# 4_digit_seven_segment.net
KiCad netlist of a schematic drawn in EAGLE
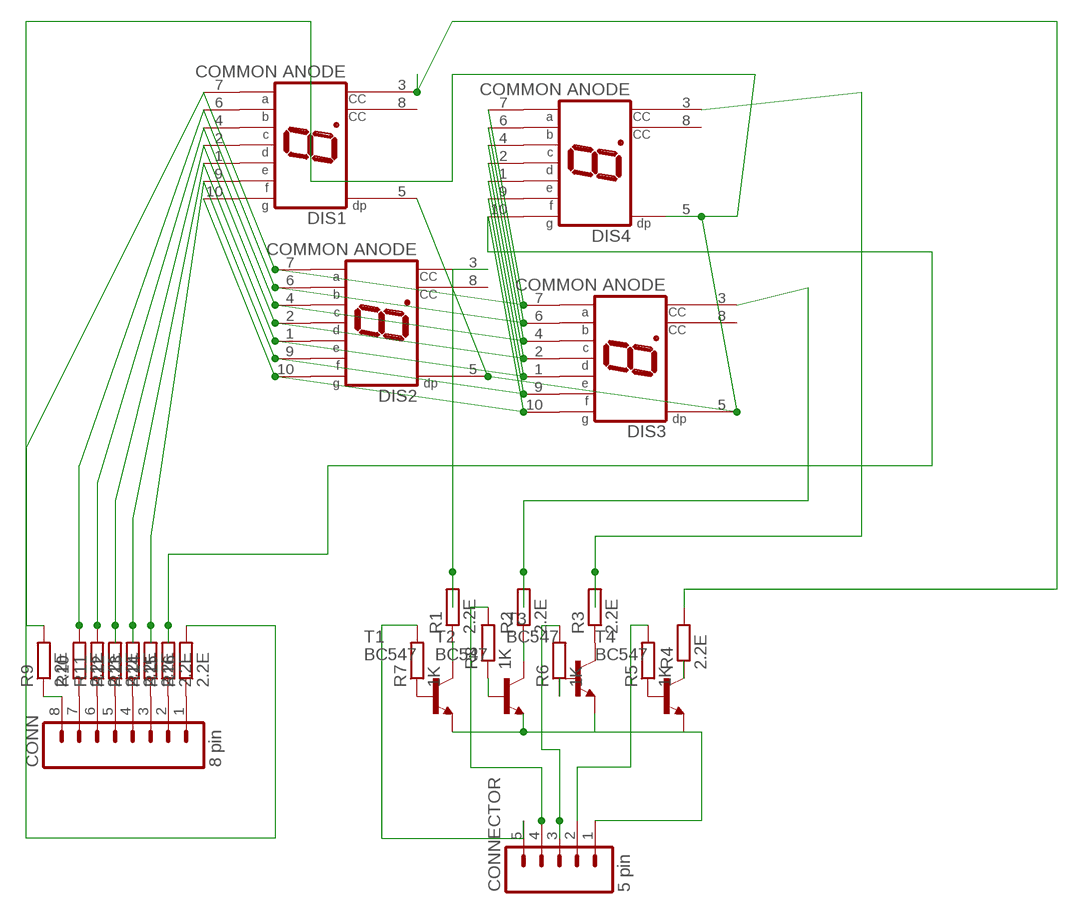
[diagram p0: schematic, sheet 1]

(export (version "E")
  (design (tool "Eeschema 10.0.6"))
  (components
    (comp (ref "CONN")
      (value "8 pin")
      (footprint "eagle-import:08P")
      (libsource (lib "eagle-import") (part "M08"))
    )
    (comp (ref "CONNECTOR")
      (value "5 pin")
      (footprint "eagle-import:05P")
      (libsource (lib "eagle-import") (part "M05"))
    )
    (comp (ref "DIS1")
      (value "COMMON ANODE")
      (footprint "eagle-import:HDSP-M")
      (libsource (lib "eagle-import") (part "HD-H103"))
    )
    (comp (ref "DIS2")
      (value "COMMON ANODE")
      (footprint "eagle-import:HDSP-M")
      (libsource (lib "eagle-import") (part "HD-H103"))
    )
    (comp (ref "DIS3")
      (value "COMMON ANODE")
      (footprint "eagle-import:HDSP-M")
      (libsource (lib "eagle-import") (part "HD-H103"))
    )
    (comp (ref "DIS4")
      (value "COMMON ANODE")
      (footprint "eagle-import:HDSP-M")
      (libsource (lib "eagle-import") (part "HD-H103"))
    )
    (comp (ref "R1")
      (value "2.2E")
      (footprint "eagle-import:0204_7")
      (libsource (lib "eagle-import") (part "R-EU_0204/7"))
    )
    (comp (ref "R2")
      (value "2.2E")
      (footprint "eagle-import:0204_7")
      (libsource (lib "eagle-import") (part "R-EU_0204/7"))
    )
    (comp (ref "R3")
      (value "2.2E")
      (footprint "eagle-import:0204_7")
      (libsource (lib "eagle-import") (part "R-EU_0204/7"))
    )
    (comp (ref "R4")
      (value "2.2E")
      (footprint "eagle-import:0204_7")
      (libsource (lib "eagle-import") (part "R-EU_0204/7"))
    )
    (comp (ref "R5")
      (value "1K")
      (footprint "eagle-import:0204_7")
      (libsource (lib "eagle-import") (part "R-EU_0204/7"))
    )
    (comp (ref "R6")
      (value "1K")
      (footprint "eagle-import:0204_7")
      (libsource (lib "eagle-import") (part "R-EU_0204/7"))
    )
    (comp (ref "R7")
      (value "1K")
      (footprint "eagle-import:0204_7")
      (libsource (lib "eagle-import") (part "R-EU_0204/7"))
    )
    (comp (ref "R8")
      (value "1K")
      (footprint "eagle-import:0204_7")
      (libsource (lib "eagle-import") (part "R-EU_0204/7"))
    )
    (comp (ref "R9")
      (value "2.2E")
      (footprint "eagle-import:0204_7")
      (libsource (lib "eagle-import") (part "R-EU_0204/7"))
    )
    (comp (ref "R10")
      (value "2.2E")
      (footprint "eagle-import:0204_7")
      (libsource (lib "eagle-import") (part "R-EU_0204/7"))
    )
    (comp (ref "R11")
      (value "2.2E")
      (footprint "eagle-import:0204_7")
      (libsource (lib "eagle-import") (part "R-EU_0204/7"))
    )
    (comp (ref "R12")
      (value "2.2E")
      (footprint "eagle-import:0204_7")
      (libsource (lib "eagle-import") (part "R-EU_0204/7"))
    )
    (comp (ref "R13")
      (value "2.2E")
      (footprint "eagle-import:0204_7")
      (libsource (lib "eagle-import") (part "R-EU_0204/7"))
    )
    (comp (ref "R14")
      (value "2.2E")
      (footprint "eagle-import:0204_7")
      (libsource (lib "eagle-import") (part "R-EU_0204/7"))
    )
    (comp (ref "R15")
      (value "2.2E")
      (footprint "eagle-import:0204_7")
      (libsource (lib "eagle-import") (part "R-EU_0204/7"))
    )
    (comp (ref "R16")
      (value "2.2E")
      (footprint "eagle-import:0204_7")
      (libsource (lib "eagle-import") (part "R-EU_0204/7"))
    )
    (comp (ref "T1")
      (value "BC547")
      (footprint "eagle-import:TO92")
      (libsource (lib "eagle-import") (part "BC547"))
    )
    (comp (ref "T2")
      (value "BC547")
      (footprint "eagle-import:TO92")
      (libsource (lib "eagle-import") (part "BC547"))
    )
    (comp (ref "T3")
      (value "BC547")
      (footprint "eagle-import:TO92")
      (libsource (lib "eagle-import") (part "BC547"))
    )
    (comp (ref "T4")
      (value "BC547")
      (footprint "eagle-import:TO92")
      (libsource (lib "eagle-import") (part "BC547"))
    )
  )
  (nets
    (net (code "1") (name "Net-(CONN-Pad1)") (class "Default")
      (node (ref "CONN") (pin "1") (pinfunction "1_1") (pintype "passive"))
      (node (ref "R16") (pin "1") (pinfunction "1_1") (pintype "passive"))
    )
    (net (code "2") (name "Net-(CONN-Pad2)") (class "Default")
      (node (ref "CONN") (pin "2") (pinfunction "2_2") (pintype "passive"))
      (node (ref "R15") (pin "1") (pinfunction "1_1") (pintype "passive"))
    )
    (net (code "3") (name "Net-(CONN-Pad3)") (class "Default")
      (node (ref "CONN") (pin "3") (pinfunction "3_3") (pintype "passive"))
      (node (ref "R14") (pin "1") (pinfunction "1_1") (pintype "passive"))
    )
    (net (code "4") (name "Net-(CONN-Pad4)") (class "Default")
      (node (ref "CONN") (pin "4") (pinfunction "4_4") (pintype "passive"))
      (node (ref "R13") (pin "1") (pinfunction "1_1") (pintype "passive"))
    )
    (net (code "5") (name "Net-(CONN-Pad5)") (class "Default")
      (node (ref "CONN") (pin "5") (pinfunction "5_5") (pintype "passive"))
      (node (ref "R12") (pin "1") (pinfunction "1_1") (pintype "passive"))
    )
    (net (code "6") (name "Net-(CONN-Pad6)") (class "Default")
      (node (ref "CONN") (pin "6") (pinfunction "6_6") (pintype "passive"))
      (node (ref "R11") (pin "1") (pinfunction "1_1") (pintype "passive"))
    )
    (net (code "7") (name "Net-(CONN-Pad7)") (class "Default")
      (node (ref "CONN") (pin "7") (pinfunction "7_7") (pintype "passive"))
      (node (ref "R10") (pin "1") (pinfunction "1_1") (pintype "passive"))
    )
    (net (code "8") (name "Net-(CONN-Pad8)") (class "Default")
      (node (ref "CONN") (pin "8") (pinfunction "8_8") (pintype "passive"))
      (node (ref "R9") (pin "1") (pinfunction "1_1") (pintype "passive"))
    )
    (net (code "9") (name "Net-(CONNECTOR-Pad2)") (class "Default")
      (node (ref "CONNECTOR") (pin "2") (pinfunction "2_2") (pintype "passive"))
      (node (ref "R5") (pin "2") (pinfunction "2_2") (pintype "passive"))
    )
    (net (code "10") (name "Net-(CONNECTOR-Pad3)") (class "Default")
      (node (ref "CONNECTOR") (pin "3") (pinfunction "3_3") (pintype "passive"))
      (node (ref "R6") (pin "2") (pinfunction "2_2") (pintype "passive"))
    )
    (net (code "11") (name "Net-(CONNECTOR-Pad4)") (class "Default")
      (node (ref "CONNECTOR") (pin "4") (pinfunction "4_4") (pintype "passive"))
      (node (ref "R8") (pin "2") (pinfunction "2_2") (pintype "passive"))
    )
    (net (code "12") (name "Net-(CONNECTOR-Pad5)") (class "Default")
      (node (ref "CONNECTOR") (pin "5") (pinfunction "5_5") (pintype "passive"))
      (node (ref "R7") (pin "2") (pinfunction "2_2") (pintype "passive"))
    )
    (net (code "13") (name "Net-(DIS1-A)") (class "Default")
      (node (ref "DIS1") (pin "7") (pinfunction "A_7") (pintype "passive"))
      (node (ref "DIS2") (pin "7") (pinfunction "A_7") (pintype "passive"))
      (node (ref "DIS3") (pin "7") (pinfunction "A_7") (pintype "passive"))
      (node (ref "DIS4") (pin "7") (pinfunction "A_7") (pintype "passive"))
      (node (ref "R9") (pin "2") (pinfunction "2_2") (pintype "passive"))
    )
    (net (code "14") (name "Net-(DIS1-B)") (class "Default")
      (node (ref "DIS1") (pin "6") (pinfunction "B_6") (pintype "passive"))
      (node (ref "DIS2") (pin "6") (pinfunction "B_6") (pintype "passive"))
      (node (ref "DIS3") (pin "6") (pinfunction "B_6") (pintype "passive"))
      (node (ref "DIS4") (pin "6") (pinfunction "B_6") (pintype "passive"))
      (node (ref "R10") (pin "2") (pinfunction "2_2") (pintype "passive"))
    )
    (net (code "15") (name "Net-(DIS1-C)") (class "Default")
      (node (ref "DIS1") (pin "4") (pinfunction "C_4") (pintype "passive"))
      (node (ref "DIS2") (pin "4") (pinfunction "C_4") (pintype "passive"))
      (node (ref "DIS3") (pin "4") (pinfunction "C_4") (pintype "passive"))
      (node (ref "DIS4") (pin "4") (pinfunction "C_4") (pintype "passive"))
      (node (ref "R11") (pin "2") (pinfunction "2_2") (pintype "passive"))
    )
    (net (code "16") (name "Net-(DIS1-CC-Pad3)") (class "Default")
      (node (ref "DIS1") (pin "3") (pinfunction "CC_3") (pintype "passive"))
      (node (ref "R4") (pin "2") (pinfunction "2_2") (pintype "passive"))
    )
    (net (code "17") (name "Net-(DIS1-D)") (class "Default")
      (node (ref "DIS1") (pin "2") (pinfunction "D_2") (pintype "passive"))
      (node (ref "DIS2") (pin "2") (pinfunction "D_2") (pintype "passive"))
      (node (ref "DIS3") (pin "2") (pinfunction "D_2") (pintype "passive"))
      (node (ref "DIS4") (pin "2") (pinfunction "D_2") (pintype "passive"))
      (node (ref "R12") (pin "2") (pinfunction "2_2") (pintype "passive"))
    )
    (net (code "18") (name "Net-(DIS1-DP)") (class "Default")
      (node (ref "DIS1") (pin "5") (pinfunction "DP_5") (pintype "passive"))
      (node (ref "DIS2") (pin "5") (pinfunction "DP_5") (pintype "passive"))
      (node (ref "DIS3") (pin "5") (pinfunction "DP_5") (pintype "passive"))
      (node (ref "DIS4") (pin "5") (pinfunction "DP_5") (pintype "passive"))
      (node (ref "R16") (pin "2") (pinfunction "2_2") (pintype "passive"))
    )
    (net (code "19") (name "Net-(DIS1-E)") (class "Default")
      (node (ref "DIS1") (pin "1") (pinfunction "E_1") (pintype "passive"))
      (node (ref "DIS2") (pin "1") (pinfunction "E_1") (pintype "passive"))
      (node (ref "DIS3") (pin "1") (pinfunction "E_1") (pintype "passive"))
      (node (ref "DIS4") (pin "1") (pinfunction "E_1") (pintype "passive"))
      (node (ref "R13") (pin "2") (pinfunction "2_2") (pintype "passive"))
    )
    (net (code "20") (name "Net-(DIS1-F)") (class "Default")
      (node (ref "DIS1") (pin "9") (pinfunction "F_9") (pintype "passive"))
      (node (ref "DIS2") (pin "9") (pinfunction "F_9") (pintype "passive"))
      (node (ref "DIS3") (pin "9") (pinfunction "F_9") (pintype "passive"))
      (node (ref "DIS4") (pin "9") (pinfunction "F_9") (pintype "passive"))
      (node (ref "R14") (pin "2") (pinfunction "2_2") (pintype "passive"))
    )
    (net (code "21") (name "Net-(DIS1-G)") (class "Default")
      (node (ref "DIS1") (pin "10") (pinfunction "G_10") (pintype "passive"))
      (node (ref "DIS2") (pin "10") (pinfunction "G_10") (pintype "passive"))
      (node (ref "DIS3") (pin "10") (pinfunction "G_10") (pintype "passive"))
      (node (ref "DIS4") (pin "10") (pinfunction "G_10") (pintype "passive"))
      (node (ref "R15") (pin "2") (pinfunction "2_2") (pintype "passive"))
    )
    (net (code "22") (name "Net-(DIS2-CC-Pad3)") (class "Default")
      (node (ref "DIS2") (pin "3") (pinfunction "CC_3") (pintype "passive"))
      (node (ref "R1") (pin "2") (pinfunction "2_2") (pintype "passive"))
    )
    (net (code "23") (name "Net-(DIS3-CC-Pad3)") (class "Default")
      (node (ref "DIS3") (pin "3") (pinfunction "CC_3") (pintype "passive"))
      (node (ref "R2") (pin "2") (pinfunction "2_2") (pintype "passive"))
    )
    (net (code "24") (name "Net-(DIS4-CC-Pad3)") (class "Default")
      (node (ref "DIS4") (pin "3") (pinfunction "CC_3") (pintype "passive"))
      (node (ref "R3") (pin "2") (pinfunction "2_2") (pintype "passive"))
    )
    (net (code "25") (name "Net-(T1-B)") (class "Default")
      (node (ref "R7") (pin "1") (pinfunction "1_1") (pintype "passive"))
      (node (ref "T1") (pin "2") (pinfunction "B_2") (pintype "passive"))
    )
    (net (code "26") (name "Net-(T1-C)") (class "Default")
      (node (ref "R1") (pin "1") (pinfunction "1_1") (pintype "passive"))
      (node (ref "T1") (pin "3") (pinfunction "C_3") (pintype "passive"))
    )
    (net (code "27") (name "Net-(T1-E)") (class "Default")
      (node (ref "CONNECTOR") (pin "1") (pinfunction "1_1") (pintype "passive"))
      (node (ref "T1") (pin "1") (pinfunction "E_1") (pintype "passive"))
      (node (ref "T2") (pin "1") (pinfunction "E_1") (pintype "passive"))
      (node (ref "T3") (pin "1") (pinfunction "E_1") (pintype "passive"))
      (node (ref "T4") (pin "1") (pinfunction "E_1") (pintype "passive"))
    )
    (net (code "28") (name "Net-(T2-B)") (class "Default")
      (node (ref "R8") (pin "1") (pinfunction "1_1") (pintype "passive"))
      (node (ref "T2") (pin "2") (pinfunction "B_2") (pintype "passive"))
    )
    (net (code "29") (name "Net-(T2-C)") (class "Default")
      (node (ref "R2") (pin "1") (pinfunction "1_1") (pintype "passive"))
      (node (ref "T2") (pin "3") (pinfunction "C_3") (pintype "passive"))
    )
    (net (code "30") (name "Net-(T3-B)") (class "Default")
      (node (ref "R6") (pin "1") (pinfunction "1_1") (pintype "passive"))
      (node (ref "T3") (pin "2") (pinfunction "B_2") (pintype "passive"))
    )
    (net (code "31") (name "Net-(T3-C)") (class "Default")
      (node (ref "R3") (pin "1") (pinfunction "1_1") (pintype "passive"))
      (node (ref "T3") (pin "3") (pinfunction "C_3") (pintype "passive"))
    )
    (net (code "32") (name "Net-(T4-B)") (class "Default")
      (node (ref "R5") (pin "1") (pinfunction "1_1") (pintype "passive"))
      (node (ref "T4") (pin "2") (pinfunction "B_2") (pintype "passive"))
    )
    (net (code "33") (name "Net-(T4-C)") (class "Default")
      (node (ref "R4") (pin "1") (pinfunction "1_1") (pintype "passive"))
      (node (ref "T4") (pin "3") (pinfunction "C_3") (pintype "passive"))
    )
    (net (code "34") (name "unconnected-(DIS1-CC-Pad8)") (class "Default")
      (node (ref "DIS1") (pin "8") (pinfunction "CC_8") (pintype "passive"))
    )
    (net (code "35") (name "unconnected-(DIS2-CC-Pad8)") (class "Default")
      (node (ref "DIS2") (pin "8") (pinfunction "CC_8") (pintype "passive"))
    )
    (net (code "36") (name "unconnected-(DIS3-CC-Pad8)") (class "Default")
      (node (ref "DIS3") (pin "8") (pinfunction "CC_8") (pintype "passive"))
    )
    (net (code "37") (name "unconnected-(DIS4-CC-Pad8)") (class "Default")
      (node (ref "DIS4") (pin "8") (pinfunction "CC_8") (pintype "passive"))
    )
  )
)
